# StEth32_Base_OLED_UserIO.net
KiCad netlist of a schematic drawn in Altium Designer
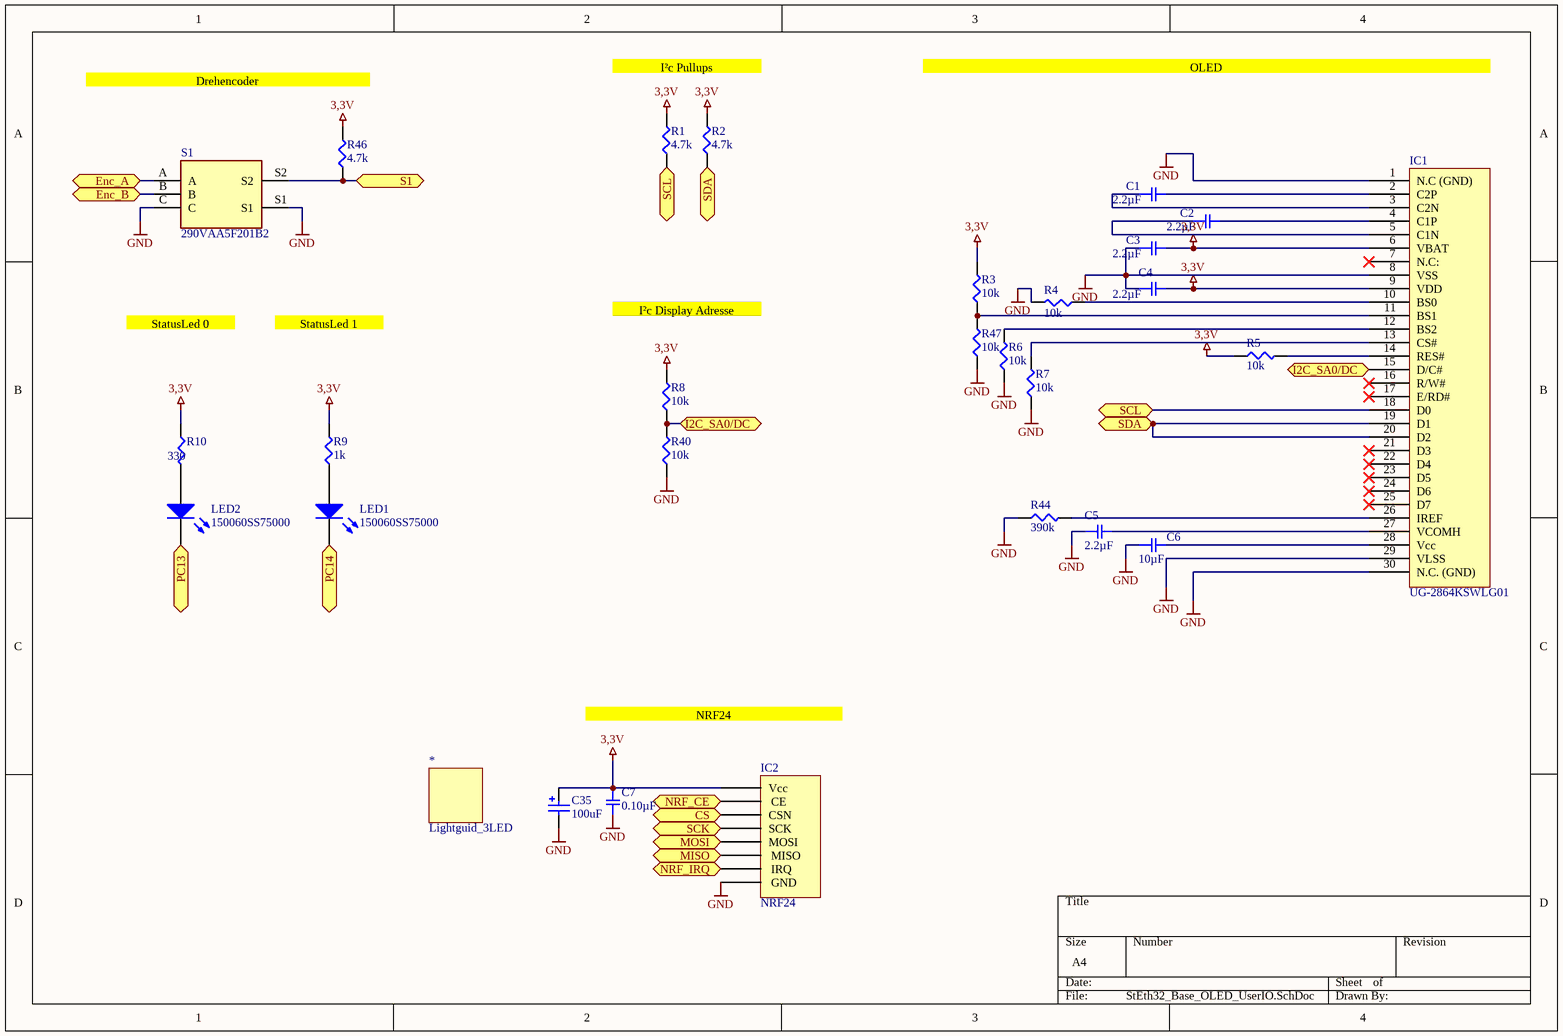
[diagram p0: StEth32_Base_OLED_UserIO.SchDoc]

(export (version "E")
  (design (tool "Eeschema 10.0.6"))
  (components
    (comp (ref "*")
      (value "Lightguid_3LED")
      (footprint "LightGuid3")
      (description "Lichtleiter 3Dach 90°")
      (libsource (lib "MyLibs") (part "Lightguid_3LED"))
    )
    (comp (ref "C1")
      (value "2.2µF")
      (footprint "SMD-0603C")
      (description "CAP CER 2.2UF 16V X6S 0603")
      (fields
        (field (name "DIGI-KEY PART NUMBER") "490-11993-1-ND")
        (field (name "PART NUMBER") "GRM188C81C225KA12D")
      )
      (libsource (lib "capacitor_murata_0603") (part "GRM188C81C225KA12D"))
    )
    (comp (ref "C2")
      (value "2.2µF")
      (footprint "SMD-0603C")
      (description "CAP CER 2.2UF 16V X6S 0603")
      (fields
        (field (name "DIGI-KEY PART NUMBER") "490-11993-1-ND")
        (field (name "PART NUMBER") "GRM188C81C225KA12D")
      )
      (libsource (lib "capacitor_murata_0603") (part "GRM188C81C225KA12D"))
    )
    (comp (ref "C3")
      (value "2.2µF")
      (footprint "SMD-0603C")
      (description "CAP CER 2.2UF 16V X6S 0603")
      (fields
        (field (name "DIGI-KEY PART NUMBER") "490-11993-1-ND")
        (field (name "PART NUMBER") "GRM188C81C225KA12D")
      )
      (libsource (lib "capacitor_murata_0603") (part "GRM188C81C225KA12D"))
    )
    (comp (ref "C4")
      (value "2.2µF")
      (footprint "SMD-0603C")
      (description "CAP CER 2.2UF 16V X6S 0603")
      (fields
        (field (name "DIGI-KEY PART NUMBER") "490-11993-1-ND")
        (field (name "PART NUMBER") "GRM188C81C225KA12D")
      )
      (libsource (lib "capacitor_murata_0603") (part "GRM188C81C225KA12D"))
    )
    (comp (ref "C5")
      (value "2.2µF")
      (footprint "SMD-0603C")
      (description "CAP CER 2.2UF 16V X6S 0603")
      (fields
        (field (name "DIGI-KEY PART NUMBER") "490-11993-1-ND")
        (field (name "PART NUMBER") "GRM188C81C225KA12D")
      )
      (libsource (lib "capacitor_murata_0603") (part "GRM188C81C225KA12D"))
    )
    (comp (ref "C6")
      (value "10µF")
      (footprint "SMD-0603C")
      (description "CAP CER 10UF 6.3V X5R 0603")
      (fields
        (field (name "DIGI-KEY PART NUMBER") "490-10467-1-ND")
        (field (name "PART NUMBER") "GRM185R60J106ME15D")
      )
      (libsource (lib "capacitor_murata_0603") (part "GRM185R60J106ME15D"))
    )
    (comp (ref "C7")
      (value "0.10µF")
      (footprint "SMD-0603C")
      (description "CAP CER 0.1UF 16V X7R 0603")
      (fields
        (field (name "DIGI-KEY PART NUMBER") "490-8015-1-ND")
        (field (name "PART NUMBER") "GCM188R71C104KA37J")
      )
      (libsource (lib "capacitor_murata_0603") (part "GCM188R71C104KA37J"))
    )
    (comp (ref "C35")
      (value "100uF")
      (footprint "WCAP-ASLI_6.3x5.5")
      (description "WCAP-ASLI Aluminum Electrolytic Capacitors, size Ф6.3x5.5mm, 10V DC, 100uF")
      (fields (field (name "PART NUMBER") "865080243007") (field (name "PUBLISHER") "Wurth Elektronik"))
      (libsource (lib "ALTIUM-WCAP-ASLI-rev17a") (part "865080243007"))
    )
    (comp (ref "IC1")
      (value "UG-2864KSWLG01")
      (footprint "UG-2864KSWLG01")
      (description "OLED 1,3\" 128x64")
      (libsource (lib "MyLibs") (part "UG-2864KSWLG01"))
    )
    (comp (ref "IC2") (value "NRF24") (footprint "ML01SP4") (libsource (lib "MyLibs") (part "NRF24")))
    (comp (ref "LED1")
      (value "150060SS75000")
      (footprint "0603_A")
      (description "SMD mono-color Chip LED, WL-SMCW, Super Red")
      (libsource (lib "WL-SMCW SMD chip LED top view mono-color waterclear") (part "150060SS75000"))
    )
    (comp (ref "LED2")
      (value "150060SS75000")
      (footprint "0603_A")
      (description "SMD mono-color Chip LED, WL-SMCW, Super Red")
      (libsource (lib "WL-SMCW SMD chip LED top view mono-color waterclear") (part "150060SS75000"))
    )
    (comp (ref "R1")
      (value "4.7k")
      (footprint "SMD-0603-RES")
      (description "RES SMD 4.7K OHM 1% 1/4W 0603")
      (fields
        (field (name "PART NUMBER") "ERJ-PA3F4701V")
        (field (name "DIGI-KEY PART NUMBER") "P4.7KBYCT-ND")
      )
      (libsource (lib "Panasonic_ERJ_0603") (part "ERJ-PA3F4701V"))
    )
    (comp (ref "R2")
      (value "4.7k")
      (footprint "SMD-0603-RES")
      (description "RES SMD 4.7K OHM 1% 1/4W 0603")
      (fields
        (field (name "PART NUMBER") "ERJ-PA3F4701V")
        (field (name "DIGI-KEY PART NUMBER") "P4.7KBYCT-ND")
      )
      (libsource (lib "Panasonic_ERJ_0603") (part "ERJ-PA3F4701V"))
    )
    (comp (ref "R3")
      (value "10k")
      (footprint "SMD-0603-RES")
      (description "RES SMD 10K OHM 1% 1/10W 0603")
      (fields
        (field (name "PART NUMBER") "ERJ-3EKF1002V")
        (field (name "DIGI-KEY PART NUMBER") "P10.0KHCT-ND")
      )
      (libsource (lib "Panasonic_ERJ_0603") (part "ERJ-3EKF1002V"))
    )
    (comp (ref "R4")
      (value "10k")
      (footprint "SMD-0603-RES")
      (description "RES SMD 10K OHM 1% 1/10W 0603")
      (fields
        (field (name "PART NUMBER") "ERJ-3EKF1002V")
        (field (name "DIGI-KEY PART NUMBER") "P10.0KHCT-ND")
      )
      (libsource (lib "Panasonic_ERJ_0603") (part "ERJ-3EKF1002V"))
    )
    (comp (ref "R5")
      (value "10k")
      (footprint "SMD-0603-RES")
      (description "RES SMD 10K OHM 1% 1/10W 0603")
      (fields
        (field (name "PART NUMBER") "ERJ-3EKF1002V")
        (field (name "DIGI-KEY PART NUMBER") "P10.0KHCT-ND")
      )
      (libsource (lib "Panasonic_ERJ_0603") (part "ERJ-3EKF1002V"))
    )
    (comp (ref "R6")
      (value "10k")
      (footprint "SMD-0603-RES")
      (description "RES SMD 10K OHM 1% 1/10W 0603")
      (fields
        (field (name "PART NUMBER") "ERJ-3EKF1002V")
        (field (name "DIGI-KEY PART NUMBER") "P10.0KHCT-ND")
      )
      (libsource (lib "Panasonic_ERJ_0603") (part "ERJ-3EKF1002V"))
    )
    (comp (ref "R7")
      (value "10k")
      (footprint "SMD-0603-RES")
      (description "RES SMD 10K OHM 1% 1/10W 0603")
      (fields
        (field (name "PART NUMBER") "ERJ-3EKF1002V")
        (field (name "DIGI-KEY PART NUMBER") "P10.0KHCT-ND")
      )
      (libsource (lib "Panasonic_ERJ_0603") (part "ERJ-3EKF1002V"))
    )
    (comp (ref "R8")
      (value "10k")
      (footprint "SMD-0603-RES")
      (description "RES SMD 10K OHM 1% 1/10W 0603")
      (fields
        (field (name "PART NUMBER") "ERJ-3EKF1002V")
        (field (name "DIGI-KEY PART NUMBER") "P10.0KHCT-ND")
      )
      (libsource (lib "Panasonic_ERJ_0603") (part "ERJ-3EKF1002V"))
    )
    (comp (ref "R9")
      (value "1k")
      (footprint "SMD-0603-RES")
      (description "RES SMD 1K OHM 1% 1/10W 0603")
      (fields
        (field (name "PART NUMBER") "ERJ-3EKF1001V")
        (field (name "DIGI-KEY PART NUMBER") "P1.00KHCT-ND")
      )
      (libsource (lib "Panasonic_ERJ_0603") (part "ERJ-3EKF1001V"))
    )
    (comp (ref "R10")
      (value "330")
      (footprint "SMD-0603-RES")
      (description "RES SMD 330 OHM 1% 1/10W 0603")
      (fields (field (name "PART NUMBER") "ERJ-3EKF3300V") (field (name "DIGI-KEY PART NUMBER") "P330HCT-ND"))
      (libsource (lib "Panasonic_ERJ_0603") (part "ERJ-3EKF3300V"))
    )
    (comp (ref "R40")
      (value "10k")
      (footprint "SMD-0603-RES")
      (description "RES SMD 10K OHM 1% 1/10W 0603")
      (fields
        (field (name "PART NUMBER") "ERJ-3EKF1002V")
        (field (name "DIGI-KEY PART NUMBER") "P10.0KHCT-ND")
      )
      (libsource (lib "Panasonic_ERJ_0603") (part "ERJ-3EKF1002V"))
    )
    (comp (ref "R44")
      (value "390k")
      (footprint "SMD-0603-RES")
      (description "RES SMD 390K OHM 1% 1/10W 0603")
      (fields
        (field (name "PART NUMBER") "ERJ-3EKF3903V")
        (field (name "DIGI-KEY PART NUMBER") "P390KHCT-ND")
      )
      (libsource (lib "Panasonic_ERJ_0603") (part "ERJ-3EKF3903V"))
    )
    (comp (ref "R46")
      (value "4.7k")
      (footprint "SMD-0603-RES")
      (description "RES SMD 4.7K OHM 1% 1/4W 0603")
      (fields
        (field (name "PART NUMBER") "ERJ-PA3F4701V")
        (field (name "DIGI-KEY PART NUMBER") "P4.7KBYCT-ND")
      )
      (libsource (lib "Panasonic_ERJ_0603") (part "ERJ-PA3F4701V"))
    )
    (comp (ref "R47")
      (value "10k")
      (footprint "SMD-0603-RES")
      (description "RES SMD 10K OHM 1% 1/10W 0603")
      (fields
        (field (name "PART NUMBER") "ERJ-3EKF1002V")
        (field (name "DIGI-KEY PART NUMBER") "P10.0KHCT-ND")
      )
      (libsource (lib "Panasonic_ERJ_0603") (part "ERJ-3EKF1002V"))
    )
    (comp (ref "S1")
      (value "290VAA5F201B2")
      (footprint "EC11B")
      (description "Switch")
      (fields
        (field (name "MOUSER PART NUMBER") "774-290VAA5F201B2")
        (field (name "RS PART NUMBER") "1774359")
      )
      (libsource (lib "MyLibs") (part "290VAA5F201B2"))
    )
  )
  (nets
    (net (code "1") (name "/CS") (class "Default")
      (node (ref "IC2") (pin "CSN") (pinfunction "CSN_CSN") (pintype "passive"))
    )
    (net (code "2") (name "/Enc_A") (class "Default")
      (node (ref "S1") (pin "A") (pinfunction "A_A") (pintype "passive"))
    )
    (net (code "3") (name "/Enc_B") (class "Default")
      (node (ref "S1") (pin "B") (pinfunction "B_B") (pintype "passive"))
    )
    (net (code "4") (name "/I2C_SA0{slash}DC") (class "Default")
      (node (ref "IC1") (pin "15") (pinfunction "D/C#_15") (pintype "passive"))
      (node (ref "R40") (pin "2") (pinfunction "2_2") (pintype "passive"))
      (node (ref "R8") (pin "1") (pinfunction "1_1") (pintype "passive"))
    )
    (net (code "5") (name "/MISO") (class "Default")
      (node (ref "IC2") (pin "MISO") (pinfunction "MISO_MISO") (pintype "passive"))
    )
    (net (code "6") (name "/MOSI") (class "Default")
      (node (ref "IC2") (pin "MOSI") (pinfunction "MOSI_MOSI") (pintype "passive"))
    )
    (net (code "7") (name "/NRF_CE") (class "Default")
      (node (ref "IC2") (pin "CE") (pinfunction "CE_CE") (pintype "passive"))
    )
    (net (code "8") (name "/NRF_IRQ") (class "Default")
      (node (ref "IC2") (pin "IRQ") (pinfunction "IRQ_IRQ") (pintype "passive"))
    )
    (net (code "9") (name "/PC13") (class "Default")
      (node (ref "LED2") (pin "1") (pinfunction "K_1") (pintype "passive"))
    )
    (net (code "10") (name "/PC14") (class "Default")
      (node (ref "LED1") (pin "1") (pinfunction "K_1") (pintype "passive"))
    )
    (net (code "11") (name "/S1") (class "Default")
      (node (ref "R46") (pin "1") (pinfunction "1_1") (pintype "passive"))
      (node (ref "S1") (pin "S2") (pinfunction "S2_S2") (pintype "passive"))
    )
    (net (code "12") (name "/SCK") (class "Default")
      (node (ref "IC2") (pin "SCK") (pinfunction "SCK_SCK") (pintype "passive"))
    )
    (net (code "13") (name "/SCL") (class "Default")
      (node (ref "IC1") (pin "18") (pinfunction "D0_18") (pintype "passive"))
      (node (ref "R1") (pin "1") (pinfunction "1_1") (pintype "passive"))
    )
    (net (code "14") (name "/SDA") (class "Default")
      (node (ref "IC1") (pin "19") (pinfunction "D1_19") (pintype "passive"))
      (node (ref "IC1") (pin "20") (pinfunction "D2_20") (pintype "passive"))
      (node (ref "R2") (pin "1") (pinfunction "1_1") (pintype "passive"))
    )
    (net (code "15") (name "3,3V") (class "Default")
      (node (ref "C3") (pin "2") (pinfunction "2_2") (pintype "passive"))
      (node (ref "C35") (pin "1") (pinfunction "P_1") (pintype "passive"))
      (node (ref "C4") (pin "2") (pinfunction "2_2") (pintype "passive"))
      (node (ref "C7") (pin "1") (pinfunction "1_1") (pintype "passive"))
      (node (ref "IC1") (pin "6") (pinfunction "VBAT_6") (pintype "passive"))
      (node (ref "IC1") (pin "9") (pinfunction "VDD_9") (pintype "passive"))
      (node (ref "IC2") (pin "Vcc") (pinfunction "Vcc_Vcc") (pintype "passive"))
      (node (ref "R1") (pin "2") (pinfunction "2_2") (pintype "passive"))
      (node (ref "R10") (pin "1") (pinfunction "1_1") (pintype "passive"))
      (node (ref "R2") (pin "2") (pinfunction "2_2") (pintype "passive"))
      (node (ref "R3") (pin "2") (pinfunction "2_2") (pintype "passive"))
      (node (ref "R46") (pin "2") (pinfunction "2_2") (pintype "passive"))
      (node (ref "R5") (pin "1") (pinfunction "1_1") (pintype "passive"))
      (node (ref "R8") (pin "2") (pinfunction "2_2") (pintype "passive"))
      (node (ref "R9") (pin "2") (pinfunction "2_2") (pintype "passive"))
    )
    (net (code "16") (name "GND") (class "Default")
      (node (ref "C3") (pin "1") (pinfunction "1_1") (pintype "passive"))
      (node (ref "C35") (pin "2") (pinfunction "N_2") (pintype "passive"))
      (node (ref "C4") (pin "1") (pinfunction "1_1") (pintype "passive"))
      (node (ref "C5") (pin "1") (pinfunction "1_1") (pintype "passive"))
      (node (ref "C6") (pin "1") (pinfunction "1_1") (pintype "passive"))
      (node (ref "C7") (pin "2") (pinfunction "2_2") (pintype "passive"))
      (node (ref "IC1") (pin "1") (pinfunction "N.C_(GND)_1") (pintype "passive"))
      (node (ref "IC1") (pin "29") (pinfunction "VLSS_29") (pintype "passive"))
      (node (ref "IC1") (pin "30") (pinfunction "N.C._(GND)_30") (pintype "passive"))
      (node (ref "IC1") (pin "8") (pinfunction "VSS_8") (pintype "passive"))
      (node (ref "IC2") (pin "Gnd") (pinfunction "GND_Gnd") (pintype "passive"))
      (node (ref "R4") (pin "2") (pinfunction "2_2") (pintype "passive"))
      (node (ref "R40") (pin "1") (pinfunction "1_1") (pintype "passive"))
      (node (ref "R44") (pin "1") (pinfunction "1_1") (pintype "passive"))
      (node (ref "R47") (pin "1") (pinfunction "1_1") (pintype "passive"))
      (node (ref "R6") (pin "1") (pinfunction "1_1") (pintype "passive"))
      (node (ref "R7") (pin "1") (pinfunction "1_1") (pintype "passive"))
      (node (ref "S1") (pin "C") (pinfunction "C_C") (pintype "passive"))
      (node (ref "S1") (pin "S1") (pinfunction "S1_S1") (pintype "passive"))
    )
    (net (code "17") (name "Net-(IC1-BS0)") (class "Default")
      (node (ref "IC1") (pin "10") (pinfunction "BS0_10") (pintype "passive"))
      (node (ref "R4") (pin "1") (pinfunction "1_1") (pintype "passive"))
    )
    (net (code "18") (name "Net-(IC1-BS1)") (class "Default")
      (node (ref "IC1") (pin "11") (pinfunction "BS1_11") (pintype "passive"))
      (node (ref "R3") (pin "1") (pinfunction "1_1") (pintype "passive"))
      (node (ref "R47") (pin "2") (pinfunction "2_2") (pintype "passive"))
    )
    (net (code "19") (name "Net-(IC1-BS2)") (class "Default")
      (node (ref "IC1") (pin "12") (pinfunction "BS2_12") (pintype "passive"))
      (node (ref "R6") (pin "2") (pinfunction "2_2") (pintype "passive"))
    )
    (net (code "20") (name "Net-(IC1-C1N)") (class "Default")
      (node (ref "C2") (pin "1") (pinfunction "1_1") (pintype "passive"))
      (node (ref "IC1") (pin "5") (pinfunction "C1N_5") (pintype "passive"))
    )
    (net (code "21") (name "Net-(IC1-C1P)") (class "Default")
      (node (ref "C2") (pin "2") (pinfunction "2_2") (pintype "passive"))
      (node (ref "IC1") (pin "4") (pinfunction "C1P_4") (pintype "passive"))
    )
    (net (code "22") (name "Net-(IC1-C2N)") (class "Default")
      (node (ref "C1") (pin "1") (pinfunction "1_1") (pintype "passive"))
      (node (ref "IC1") (pin "3") (pinfunction "C2N_3") (pintype "passive"))
    )
    (net (code "23") (name "Net-(IC1-C2P)") (class "Default")
      (node (ref "C1") (pin "2") (pinfunction "2_2") (pintype "passive"))
      (node (ref "IC1") (pin "2") (pinfunction "C2P_2") (pintype "passive"))
    )
    (net (code "24") (name "Net-(IC1-CS#)") (class "Default")
      (node (ref "IC1") (pin "13") (pinfunction "CS#_13") (pintype "passive"))
      (node (ref "R7") (pin "2") (pinfunction "2_2") (pintype "passive"))
    )
    (net (code "25") (name "Net-(IC1-IREF)") (class "Default")
      (node (ref "IC1") (pin "26") (pinfunction "IREF_26") (pintype "passive"))
      (node (ref "R44") (pin "2") (pinfunction "2_2") (pintype "passive"))
    )
    (net (code "26") (name "Net-(IC1-RES#)") (class "Default")
      (node (ref "IC1") (pin "14") (pinfunction "RES#_14") (pintype "passive"))
      (node (ref "R5") (pin "2") (pinfunction "2_2") (pintype "passive"))
    )
    (net (code "27") (name "Net-(IC1-VCOMH)") (class "Default")
      (node (ref "C5") (pin "2") (pinfunction "2_2") (pintype "passive"))
      (node (ref "IC1") (pin "27") (pinfunction "VCOMH_27") (pintype "passive"))
    )
    (net (code "28") (name "Net-(IC1-Vcc)") (class "Default")
      (node (ref "C6") (pin "2") (pinfunction "2_2") (pintype "passive"))
      (node (ref "IC1") (pin "28") (pinfunction "Vcc_28") (pintype "passive"))
    )
    (net (code "29") (name "Net-(LED1-A)") (class "Default")
      (node (ref "LED1") (pin "2") (pinfunction "A_2") (pintype "passive"))
      (node (ref "R9") (pin "1") (pinfunction "1_1") (pintype "passive"))
    )
    (net (code "30") (name "Net-(LED2-A)") (class "Default")
      (node (ref "LED2") (pin "2") (pinfunction "A_2") (pintype "passive"))
      (node (ref "R10") (pin "2") (pinfunction "2_2") (pintype "passive"))
    )
    (net (code "31") (name "unconnected-(IC1-D3-Pad21)") (class "Default")
      (node (ref "IC1") (pin "21") (pinfunction "D3_21") (pintype "passive+no_connect"))
    )
    (net (code "32") (name "unconnected-(IC1-D4-Pad22)") (class "Default")
      (node (ref "IC1") (pin "22") (pinfunction "D4_22") (pintype "passive+no_connect"))
    )
    (net (code "33") (name "unconnected-(IC1-D5-Pad23)") (class "Default")
      (node (ref "IC1") (pin "23") (pinfunction "D5_23") (pintype "passive+no_connect"))
    )
    (net (code "34") (name "unconnected-(IC1-D6-Pad24)") (class "Default")
      (node (ref "IC1") (pin "24") (pinfunction "D6_24") (pintype "passive+no_connect"))
    )
    (net (code "35") (name "unconnected-(IC1-D7-Pad25)") (class "Default")
      (node (ref "IC1") (pin "25") (pinfunction "D7_25") (pintype "passive+no_connect"))
    )
    (net (code "36") (name "unconnected-(IC1-E{slash}RD#-Pad17)") (class "Default")
      (node (ref "IC1") (pin "17") (pinfunction "E/RD#_17") (pintype "passive+no_connect"))
    )
    (net (code "37") (name "unconnected-(IC1-N.C:-Pad7)") (class "Default")
      (node (ref "IC1") (pin "7") (pinfunction "N.C:_7") (pintype "passive+no_connect"))
    )
    (net (code "38") (name "unconnected-(IC1-R{slash}W#-Pad16)") (class "Default")
      (node (ref "IC1") (pin "16") (pinfunction "R/W#_16") (pintype "passive+no_connect"))
    )
  )
)
